# main2.net
KiCad netlist of a schematic drawn in EAGLE
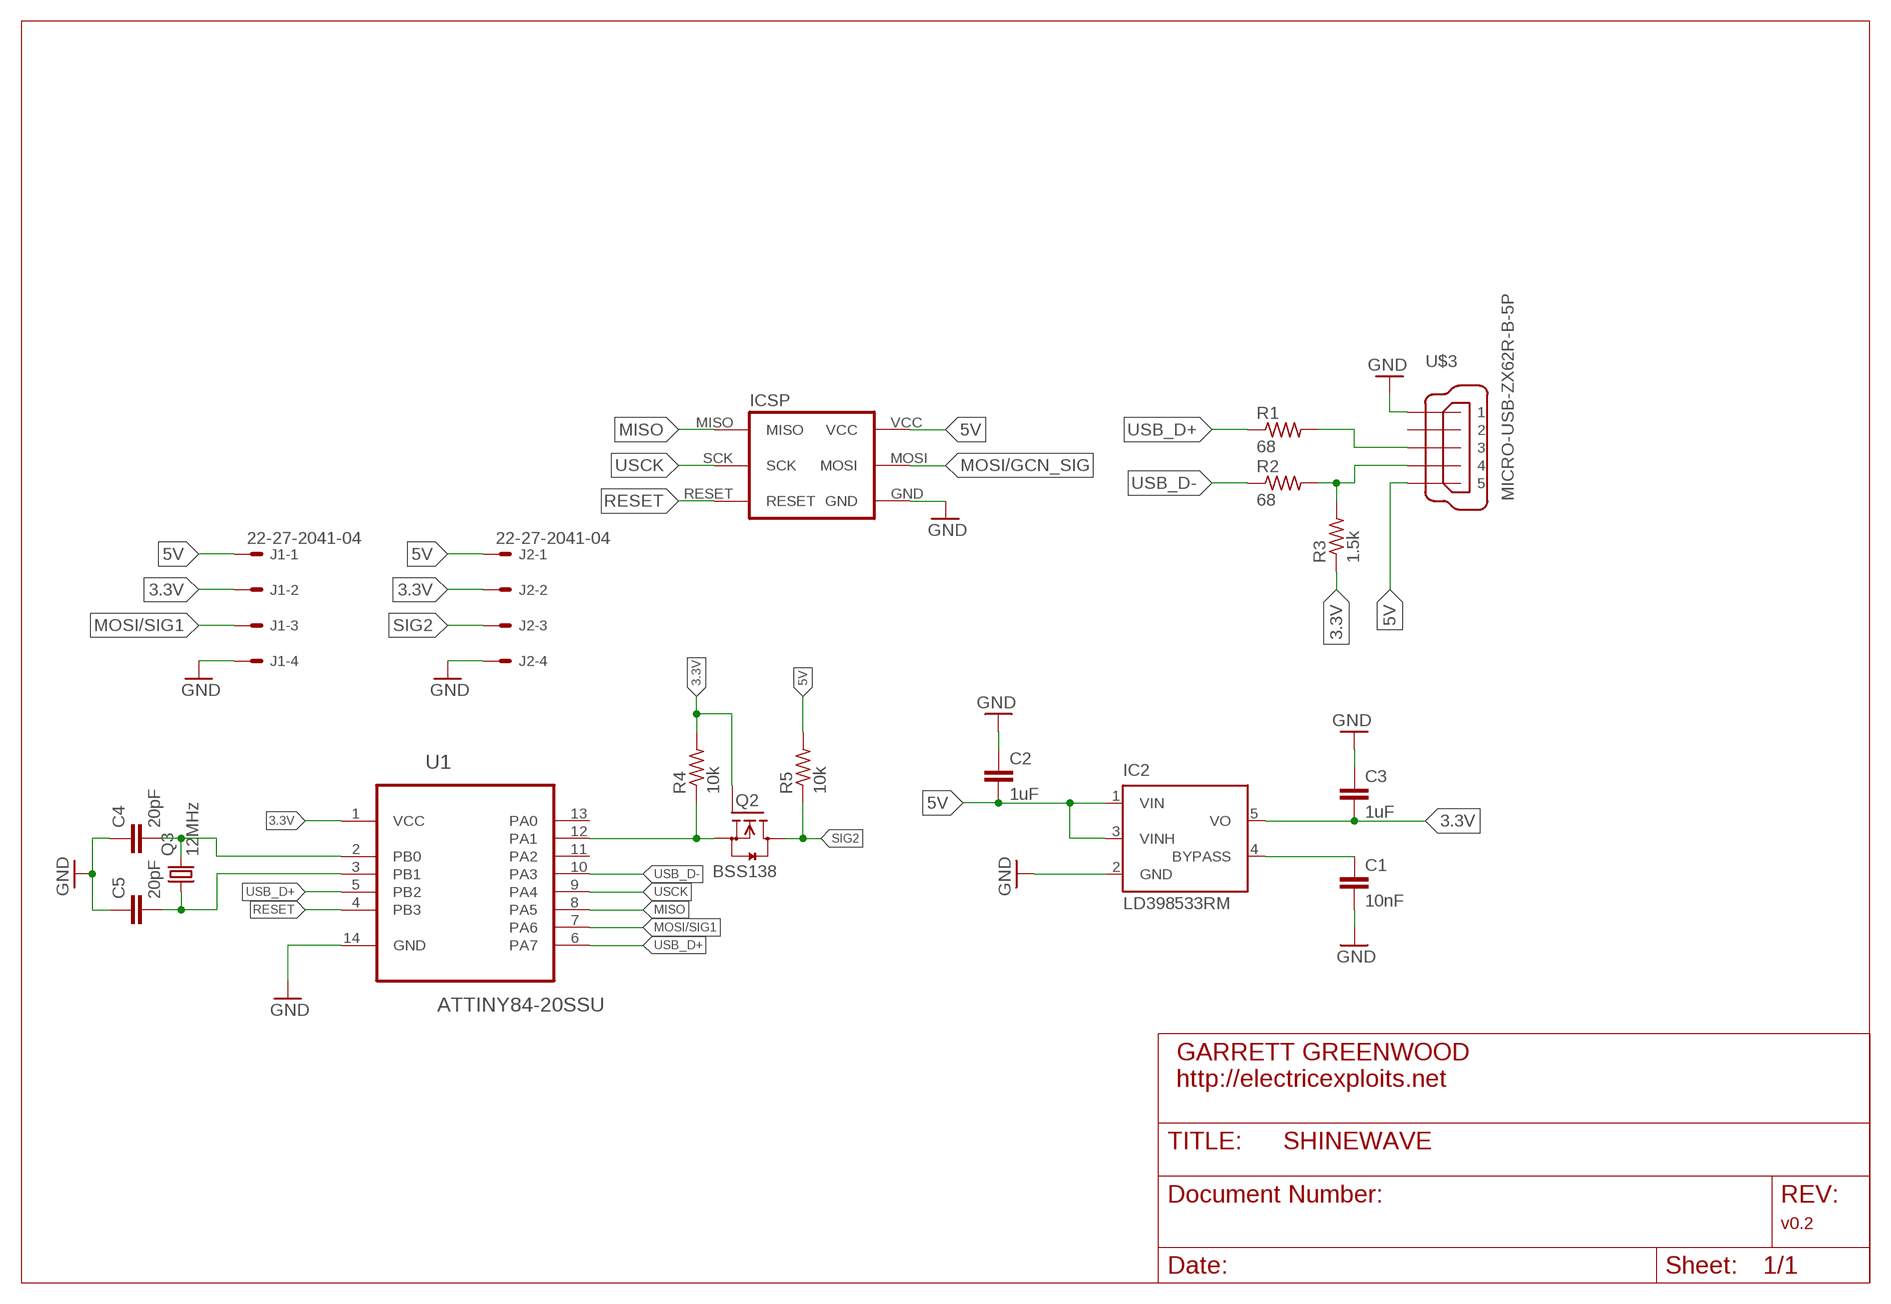
[diagram p0: schematic, sheet 1]

(export (version "E")
  (design (tool "Eeschema 10.0.6"))
  (components
    (comp (ref "C1")
      (value "10nF")
      (footprint "eagle-import:C0603")
      (libsource (lib "eagle-import") (part "C-EUC0603"))
    )
    (comp (ref "C2")
      (value "1uF")
      (footprint "eagle-import:C0603")
      (libsource (lib "eagle-import") (part "C-EUC0603"))
    )
    (comp (ref "C3")
      (value "1uF")
      (footprint "eagle-import:C0603")
      (libsource (lib "eagle-import") (part "C-EUC0603"))
    )
    (comp (ref "C4")
      (value "20pF")
      (footprint "eagle-import:C0603")
      (libsource (lib "eagle-import") (part "C-EUC0603"))
    )
    (comp (ref "C5")
      (value "20pF")
      (footprint "eagle-import:C0603")
      (libsource (lib "eagle-import") (part "C-EUC0603"))
    )
    (comp (ref "IC2")
      (value "LD398533RM")
      (footprint "eagle-import:SOT23-5L")
      (libsource (lib "eagle-import") (part "LD3985M33R"))
    )
    (comp (ref "J1")
      (value "22-27-2041-04")
      (footprint "eagle-import:6410-04")
      (libsource (lib "eagle-import") (part "22-?-0427-2041"))
    )
    (comp (ref "J2")
      (value "22-27-2041-04")
      (footprint "eagle-import:6410-04")
      (libsource (lib "eagle-import") (part "22-?-0427-2041"))
    )
    (comp (ref "Q2")
      (value "BSS138")
      (footprint "eagle-import:SOT23")
      (libsource (lib "eagle-import") (part "BSS138"))
    )
    (comp (ref "Q3")
      (value "12MHz")
      (footprint "eagle-import:CTS406")
      (libsource (lib "eagle-import") (part "CRYSTALCTS406"))
    )
    (comp (ref "R1")
      (value "68")
      (footprint "eagle-import:R0603")
      (libsource (lib "eagle-import") (part "R-US_R0603"))
    )
    (comp (ref "R2")
      (value "68")
      (footprint "eagle-import:R0603")
      (libsource (lib "eagle-import") (part "R-US_R0603"))
    )
    (comp (ref "R3")
      (value "1.5k")
      (footprint "eagle-import:R0603")
      (libsource (lib "eagle-import") (part "R-US_R0603"))
    )
    (comp (ref "R4")
      (value "10k")
      (footprint "eagle-import:R0603")
      (libsource (lib "eagle-import") (part "R-US_R0603"))
    )
    (comp (ref "R5")
      (value "10k")
      (footprint "eagle-import:R0603")
      (libsource (lib "eagle-import") (part "R-US_R0603"))
    )
    (comp (ref "U$1")
      (value "ICSP_POGO_INTERFACE")
      (footprint "eagle-import:ICSP_SMD")
      (libsource (lib "eagle-import") (part "ICSP_POGO_INTERFACE"))
    )
    (comp (ref "U$3")
      (value "MICRO-USB-ZX62R-B-5P")
      (footprint "eagle-import:ZX62R-B-5P")
      (libsource (lib "eagle-import") (part "MICRO-USB-ZX62R-B-5P"))
    )
    (comp (ref "U1")
      (value "ATTINY84-20SSU")
      (footprint "eagle-import:SOIC127P600X175-14N")
      (libsource (lib "eagle-import") (part "ATTINY84-20SSU"))
    )
  )
  (nets
    (net (code "1") (name "3.3V") (class "Default")
      (node (ref "C3") (pin "2") (pinfunction "2_2") (pintype "passive"))
      (node (ref "IC2") (pin "5") (pinfunction "VO_5") (pintype "output"))
      (node (ref "J1") (pin "2") (pinfunction "S_2") (pintype "passive"))
      (node (ref "J2") (pin "2") (pinfunction "S_2") (pintype "passive"))
      (node (ref "Q2") (pin "1") (pinfunction "G_1") (pintype "passive"))
      (node (ref "R3") (pin "1") (pinfunction "1_1") (pintype "passive"))
      (node (ref "R4") (pin "2") (pinfunction "2_2") (pintype "passive"))
      (node (ref "U1") (pin "1") (pinfunction "VCC_1") (pintype "power_in"))
    )
    (net (code "2") (name "5V") (class "Default")
      (node (ref "C2") (pin "2") (pinfunction "2_2") (pintype "passive"))
      (node (ref "IC2") (pin "1") (pinfunction "VIN_1") (pintype "input"))
      (node (ref "IC2") (pin "3") (pinfunction "VINH_3") (pintype "input"))
      (node (ref "J1") (pin "1") (pinfunction "S_1") (pintype "passive"))
      (node (ref "J2") (pin "1") (pinfunction "S_1") (pintype "passive"))
      (node (ref "R5") (pin "2") (pinfunction "2_2") (pintype "passive"))
      (node (ref "U$1") (pin "VCC") (pinfunction "VCC_VCC") (pintype "bidirectional"))
      (node (ref "U$3") (pin "5") (pinfunction "5_5") (pintype "input"))
    )
    (net (code "3") (name "GND") (class "Default")
      (node (ref "C1") (pin "2") (pinfunction "2_2") (pintype "passive"))
      (node (ref "C2") (pin "1") (pinfunction "1_1") (pintype "passive"))
      (node (ref "C3") (pin "1") (pinfunction "1_1") (pintype "passive"))
      (node (ref "C4") (pin "1") (pinfunction "1_1") (pintype "passive"))
      (node (ref "C5") (pin "1") (pinfunction "1_1") (pintype "passive"))
      (node (ref "IC2") (pin "2") (pinfunction "GND_2") (pintype "power_in"))
      (node (ref "J1") (pin "4") (pinfunction "S_4") (pintype "passive"))
      (node (ref "J2") (pin "4") (pinfunction "S_4") (pintype "passive"))
      (node (ref "U$1") (pin "GND") (pinfunction "GND_GND") (pintype "bidirectional"))
      (node (ref "U$3") (pin "1") (pinfunction "1_1") (pintype "input"))
      (node (ref "U1") (pin "14") (pinfunction "GND_14") (pintype "passive"))
    )
    (net (code "4") (name "MISO") (class "Default")
      (node (ref "U$1") (pin "MISO") (pinfunction "MISO_MISO") (pintype "bidirectional"))
      (node (ref "U1") (pin "8") (pinfunction "PA5_8") (pintype "bidirectional"))
    )
    (net (code "5") (name "MOSI{slash}GCN_SIG") (class "Default")
      (node (ref "U$1") (pin "MOSI") (pinfunction "MOSI_MOSI") (pintype "bidirectional"))
    )
    (net (code "6") (name "MOSI{slash}SIG1") (class "Default")
      (node (ref "J1") (pin "3") (pinfunction "S_3") (pintype "passive"))
      (node (ref "U1") (pin "7") (pinfunction "PA6_7") (pintype "bidirectional"))
    )
    (net (code "7") (name "Net-(IC2-BYPASS)") (class "Default")
      (node (ref "C1") (pin "1") (pinfunction "1_1") (pintype "passive"))
      (node (ref "IC2") (pin "4") (pinfunction "BYPASS_4") (pintype "passive"))
    )
    (net (code "8") (name "Net-(Q2-S)") (class "Default")
      (node (ref "Q2") (pin "2") (pinfunction "S_2") (pintype "passive"))
      (node (ref "R4") (pin "1") (pinfunction "1_1") (pintype "passive"))
      (node (ref "U1") (pin "12") (pinfunction "PA1_12") (pintype "bidirectional"))
    )
    (net (code "9") (name "Net-(Q3-2)") (class "Default")
      (node (ref "C4") (pin "2") (pinfunction "2_2") (pintype "passive"))
      (node (ref "Q3") (pin "3") (pinfunction "2_3") (pintype "passive"))
      (node (ref "U1") (pin "2") (pinfunction "PB0_2") (pintype "bidirectional"))
    )
    (net (code "10") (name "Net-(R1-Pad2)") (class "Default")
      (node (ref "R1") (pin "2") (pinfunction "2_2") (pintype "passive"))
      (node (ref "U$3") (pin "3") (pinfunction "3_3") (pintype "input"))
    )
    (net (code "11") (name "Net-(R2-Pad2)") (class "Default")
      (node (ref "R2") (pin "2") (pinfunction "2_2") (pintype "passive"))
      (node (ref "R3") (pin "2") (pinfunction "2_2") (pintype "passive"))
      (node (ref "U$3") (pin "4") (pinfunction "4_4") (pintype "input"))
    )
    (net (code "12") (name "Net-(U1-PB1)") (class "Default")
      (node (ref "C5") (pin "2") (pinfunction "2_2") (pintype "passive"))
      (node (ref "Q3") (pin "1") (pinfunction "1_1") (pintype "passive"))
      (node (ref "U1") (pin "3") (pinfunction "PB1_3") (pintype "bidirectional"))
    )
    (net (code "13") (name "RESET") (class "Default")
      (node (ref "U$1") (pin "RESET") (pinfunction "RESET_RESET") (pintype "bidirectional"))
      (node (ref "U1") (pin "4") (pinfunction "PB3_4") (pintype "bidirectional"))
    )
    (net (code "14") (name "SIG2") (class "Default")
      (node (ref "J2") (pin "3") (pinfunction "S_3") (pintype "passive"))
      (node (ref "Q2") (pin "3") (pinfunction "D_3") (pintype "passive"))
      (node (ref "R5") (pin "1") (pinfunction "1_1") (pintype "passive"))
    )
    (net (code "15") (name "USB_D+") (class "Default")
      (node (ref "R1") (pin "1") (pinfunction "1_1") (pintype "passive"))
      (node (ref "U1") (pin "5") (pinfunction "PB2_5") (pintype "bidirectional"))
      (node (ref "U1") (pin "6") (pinfunction "PA7_6") (pintype "bidirectional"))
    )
    (net (code "16") (name "USB_D-") (class "Default")
      (node (ref "R2") (pin "1") (pinfunction "1_1") (pintype "passive"))
      (node (ref "U1") (pin "10") (pinfunction "PA3_10") (pintype "bidirectional"))
    )
    (net (code "17") (name "USCK") (class "Default")
      (node (ref "U$1") (pin "SCK") (pinfunction "SCK_SCK") (pintype "bidirectional"))
      (node (ref "U1") (pin "9") (pinfunction "PA4_9") (pintype "bidirectional"))
    )
    (net (code "18") (name "unconnected-(U$3-Pad2)") (class "Default")
      (node (ref "U$3") (pin "2") (pinfunction "2_2") (pintype "input"))
    )
    (net (code "19") (name "unconnected-(U1-PA0-Pad13)") (class "Default")
      (node (ref "U1") (pin "13") (pinfunction "PA0_13") (pintype "bidirectional"))
    )
    (net (code "20") (name "unconnected-(U1-PA2-Pad11)") (class "Default")
      (node (ref "U1") (pin "11") (pinfunction "PA2_11") (pintype "bidirectional"))
    )
  )
)
